# RedBot_Line_Sensor.net
KiCad netlist of a schematic drawn in EAGLE
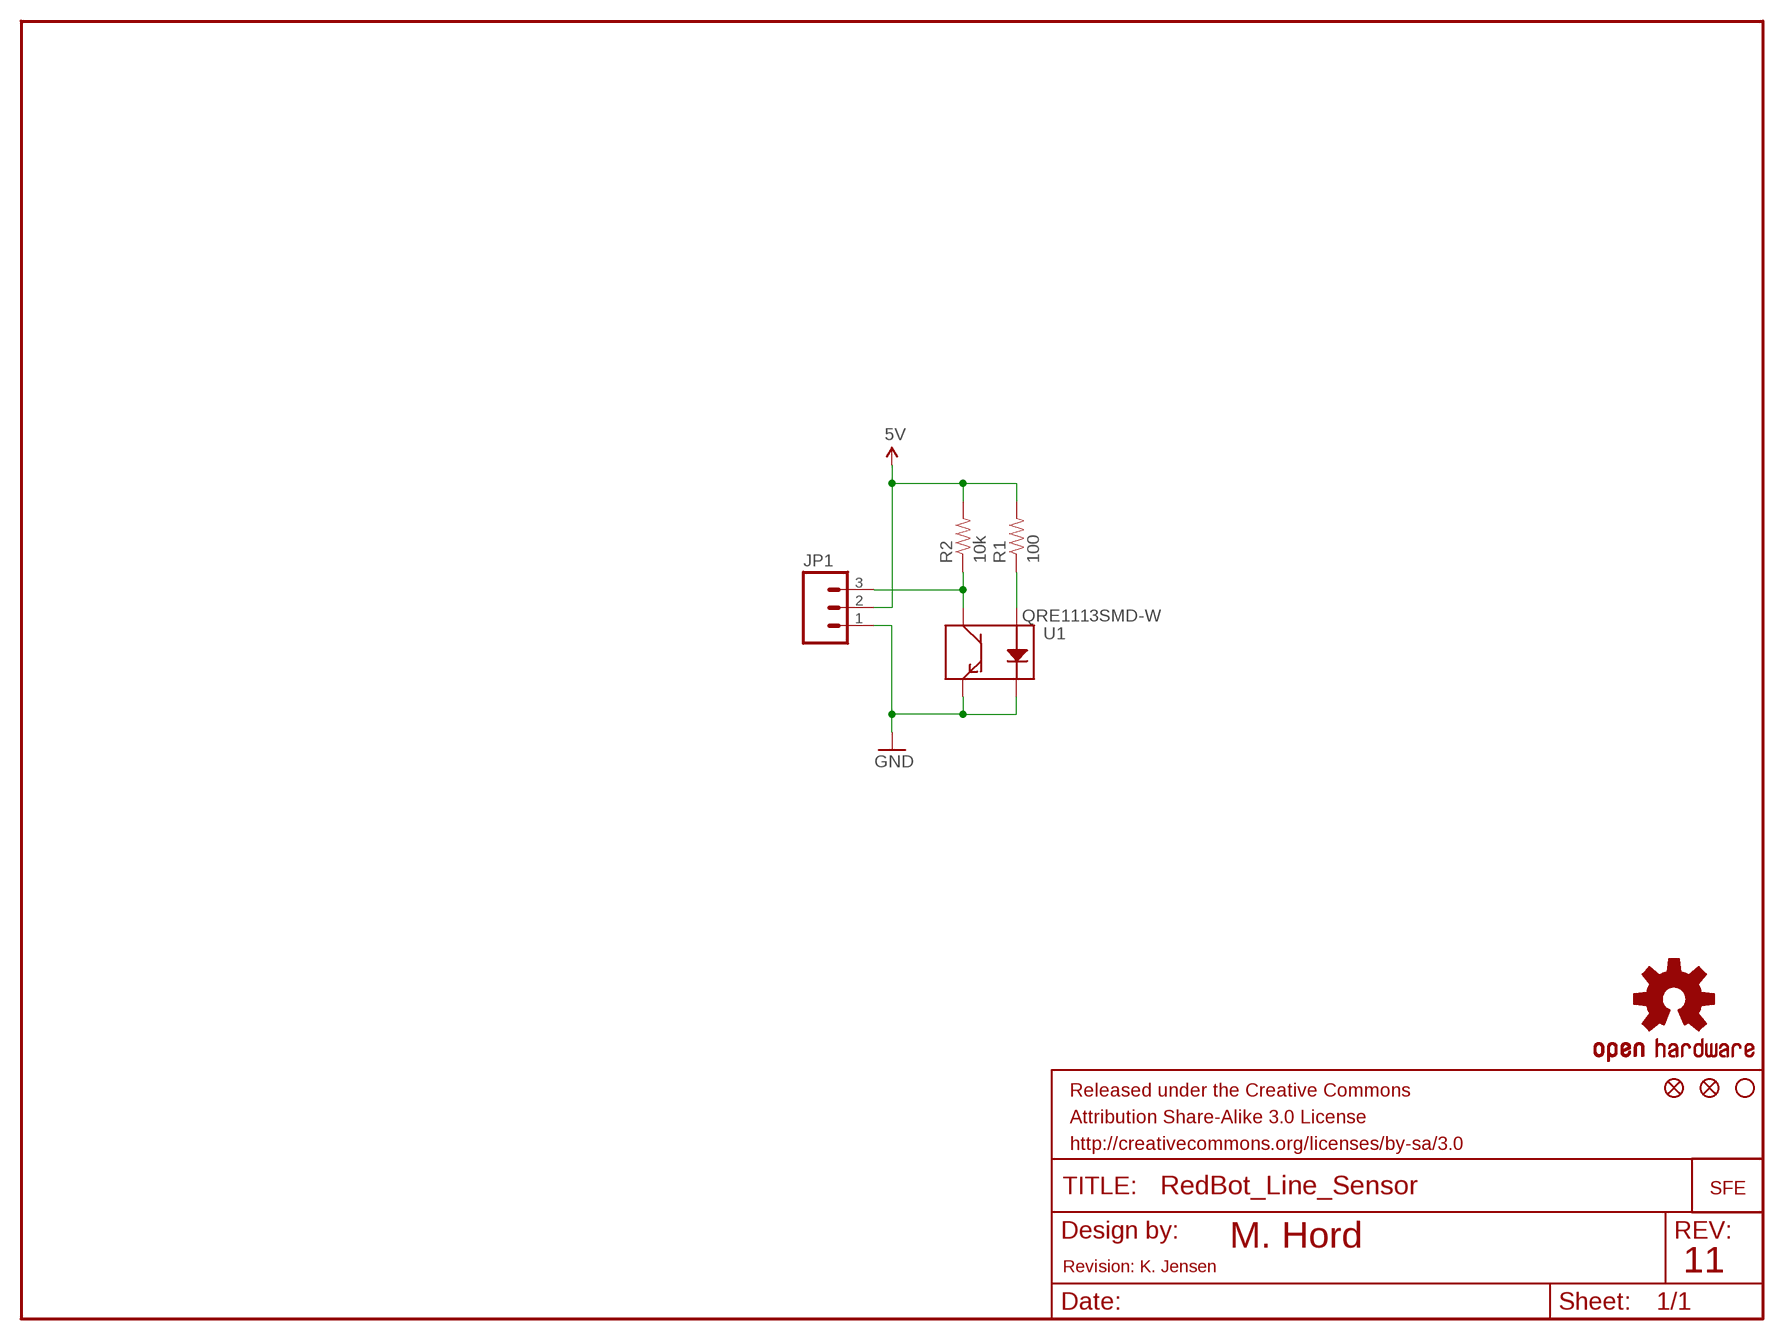
[diagram p0: schematic, sheet 1]

(export (version "E")
  (design (tool "Eeschema 10.0.6"))
  (components
    (comp (ref "FID1")
      (value "FIDUCIAL1X2")
      (footprint "eagle-import:FIDUCIAL-1X2")
      (libsource (lib "eagle-import") (part "FIDUCIAL1X2"))
    )
    (comp (ref "FID2")
      (value "FIDUCIAL1X2")
      (footprint "eagle-import:FIDUCIAL-1X2")
      (libsource (lib "eagle-import") (part "FIDUCIAL1X2"))
    )
    (comp (ref "FRAME1")
      (value "FRAME-LETTER")
      (footprint "eagle-import:CREATIVE_COMMONS")
      (libsource (lib "eagle-import") (part "FRAME-LETTER"))
    )
    (comp (ref "JP1")
      (value "M031X03_SMD_RA_MALE_POST_SMALLER")
      (footprint "eagle-import:1X03_SMD_RA_MALE_POST_SMALLER")
      (libsource (lib "eagle-import") (part "M031X03_SMD_RA_MALE_POST_SMALLER"))
    )
    (comp (ref "LOGO2")
      (value "OSHW-LOGOS")
      (footprint "eagle-import:OSHW-LOGO-S")
      (libsource (lib "eagle-import") (part "OSHW-LOGOS"))
    )
    (comp (ref "LOGO3")
      (value "LOGO-SFESK")
      (footprint "eagle-import:SFE-LOGO-FLAME")
      (libsource (lib "eagle-import") (part "LOGO-SFESK"))
    )
    (comp (ref "R1")
      (value "100")
      (footprint "eagle-import:0603-RES")
      (libsource (lib "eagle-import") (part "100-1%"))
    )
    (comp (ref "R2")
      (value "10k")
      (footprint "eagle-import:0603-RES")
      (libsource (lib "eagle-import") (part "10KOHM1/10W1%(0603)0603"))
    )
    (comp (ref "STANDOFF1")
      (value "STAND-OFF")
      (footprint "eagle-import:STAND-OFF")
      (libsource (lib "eagle-import") (part "STAND-OFF"))
    )
    (comp (ref "U1")
      (value "QRE1113SMD-W")
      (footprint "eagle-import:QRE1113-W")
      (libsource (lib "eagle-import") (part "QRE1113SMD-W"))
    )
  )
  (nets
    (net (code "1") (name "5V") (class "Default")
      (node (ref "JP1") (pin "2") (pinfunction "2_2") (pintype "passive"))
      (node (ref "R1") (pin "2") (pinfunction "2_2") (pintype "passive"))
      (node (ref "R2") (pin "2") (pinfunction "2_2") (pintype "passive"))
    )
    (net (code "2") (name "GND") (class "Default")
      (node (ref "JP1") (pin "1") (pinfunction "1_1") (pintype "passive"))
      (node (ref "U1") (pin "2") (pinfunction "K_2") (pintype "bidirectional"))
      (node (ref "U1") (pin "4") (pinfunction "E_4") (pintype "bidirectional"))
    )
    (net (code "3") (name "Net-(U1-A)") (class "Default")
      (node (ref "R1") (pin "1") (pinfunction "1_1") (pintype "passive"))
      (node (ref "U1") (pin "1") (pinfunction "A_1") (pintype "bidirectional"))
    )
    (net (code "4") (name "Net-(U1-C)") (class "Default")
      (node (ref "JP1") (pin "3") (pinfunction "3_3") (pintype "passive"))
      (node (ref "R2") (pin "1") (pinfunction "1_1") (pintype "passive"))
      (node (ref "U1") (pin "3") (pinfunction "C_3") (pintype "bidirectional"))
    )
  )
)
